# buttons.net
KiCad netlist of a schematic drawn in EAGLE
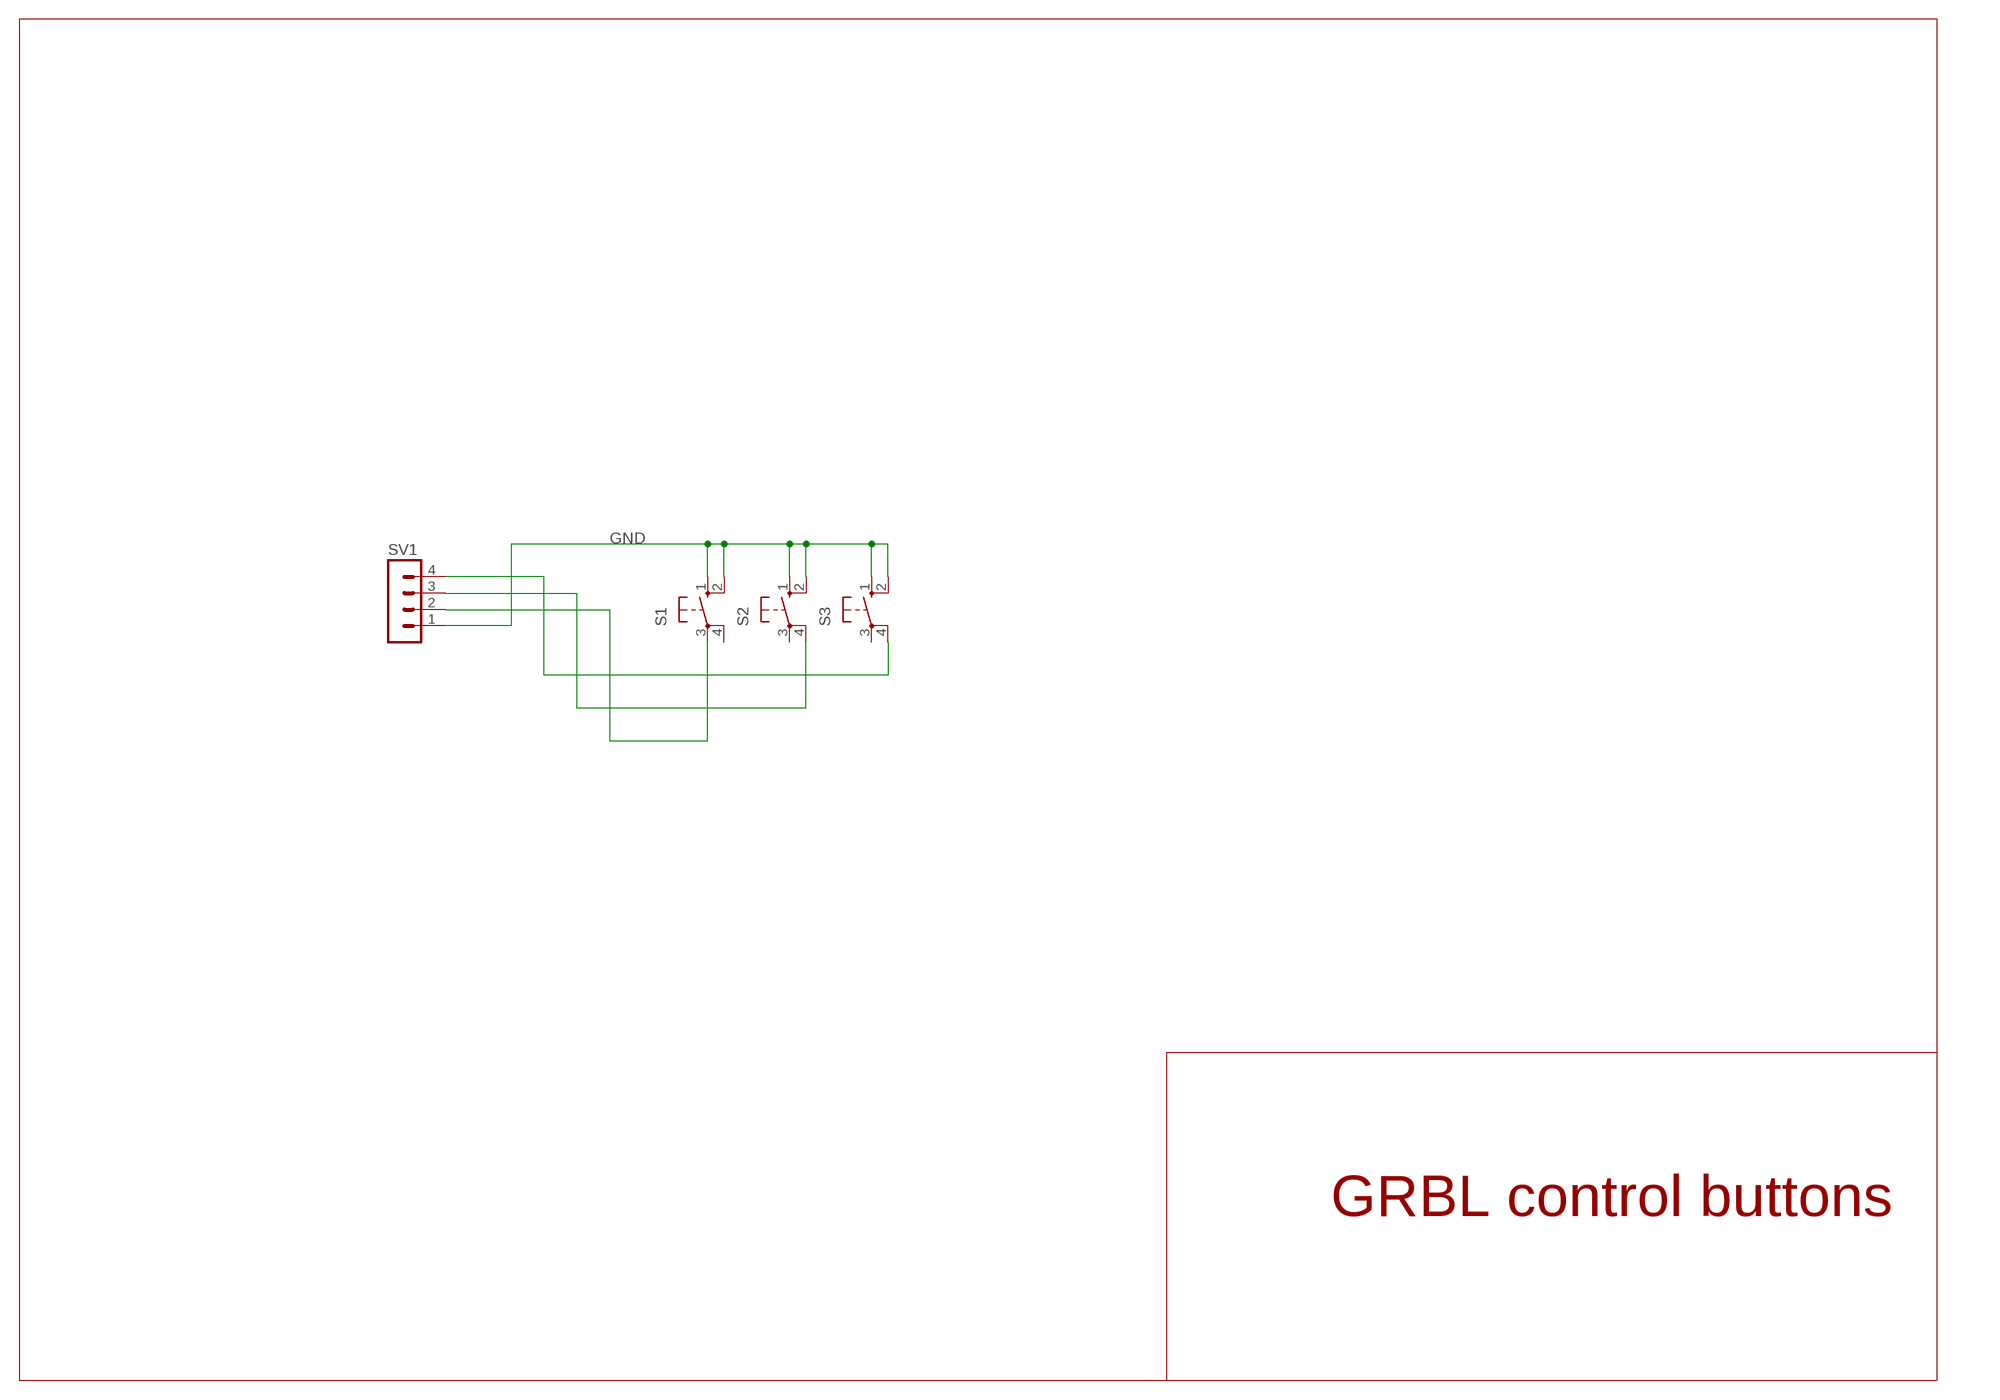
[diagram p0: schematic, sheet 1]
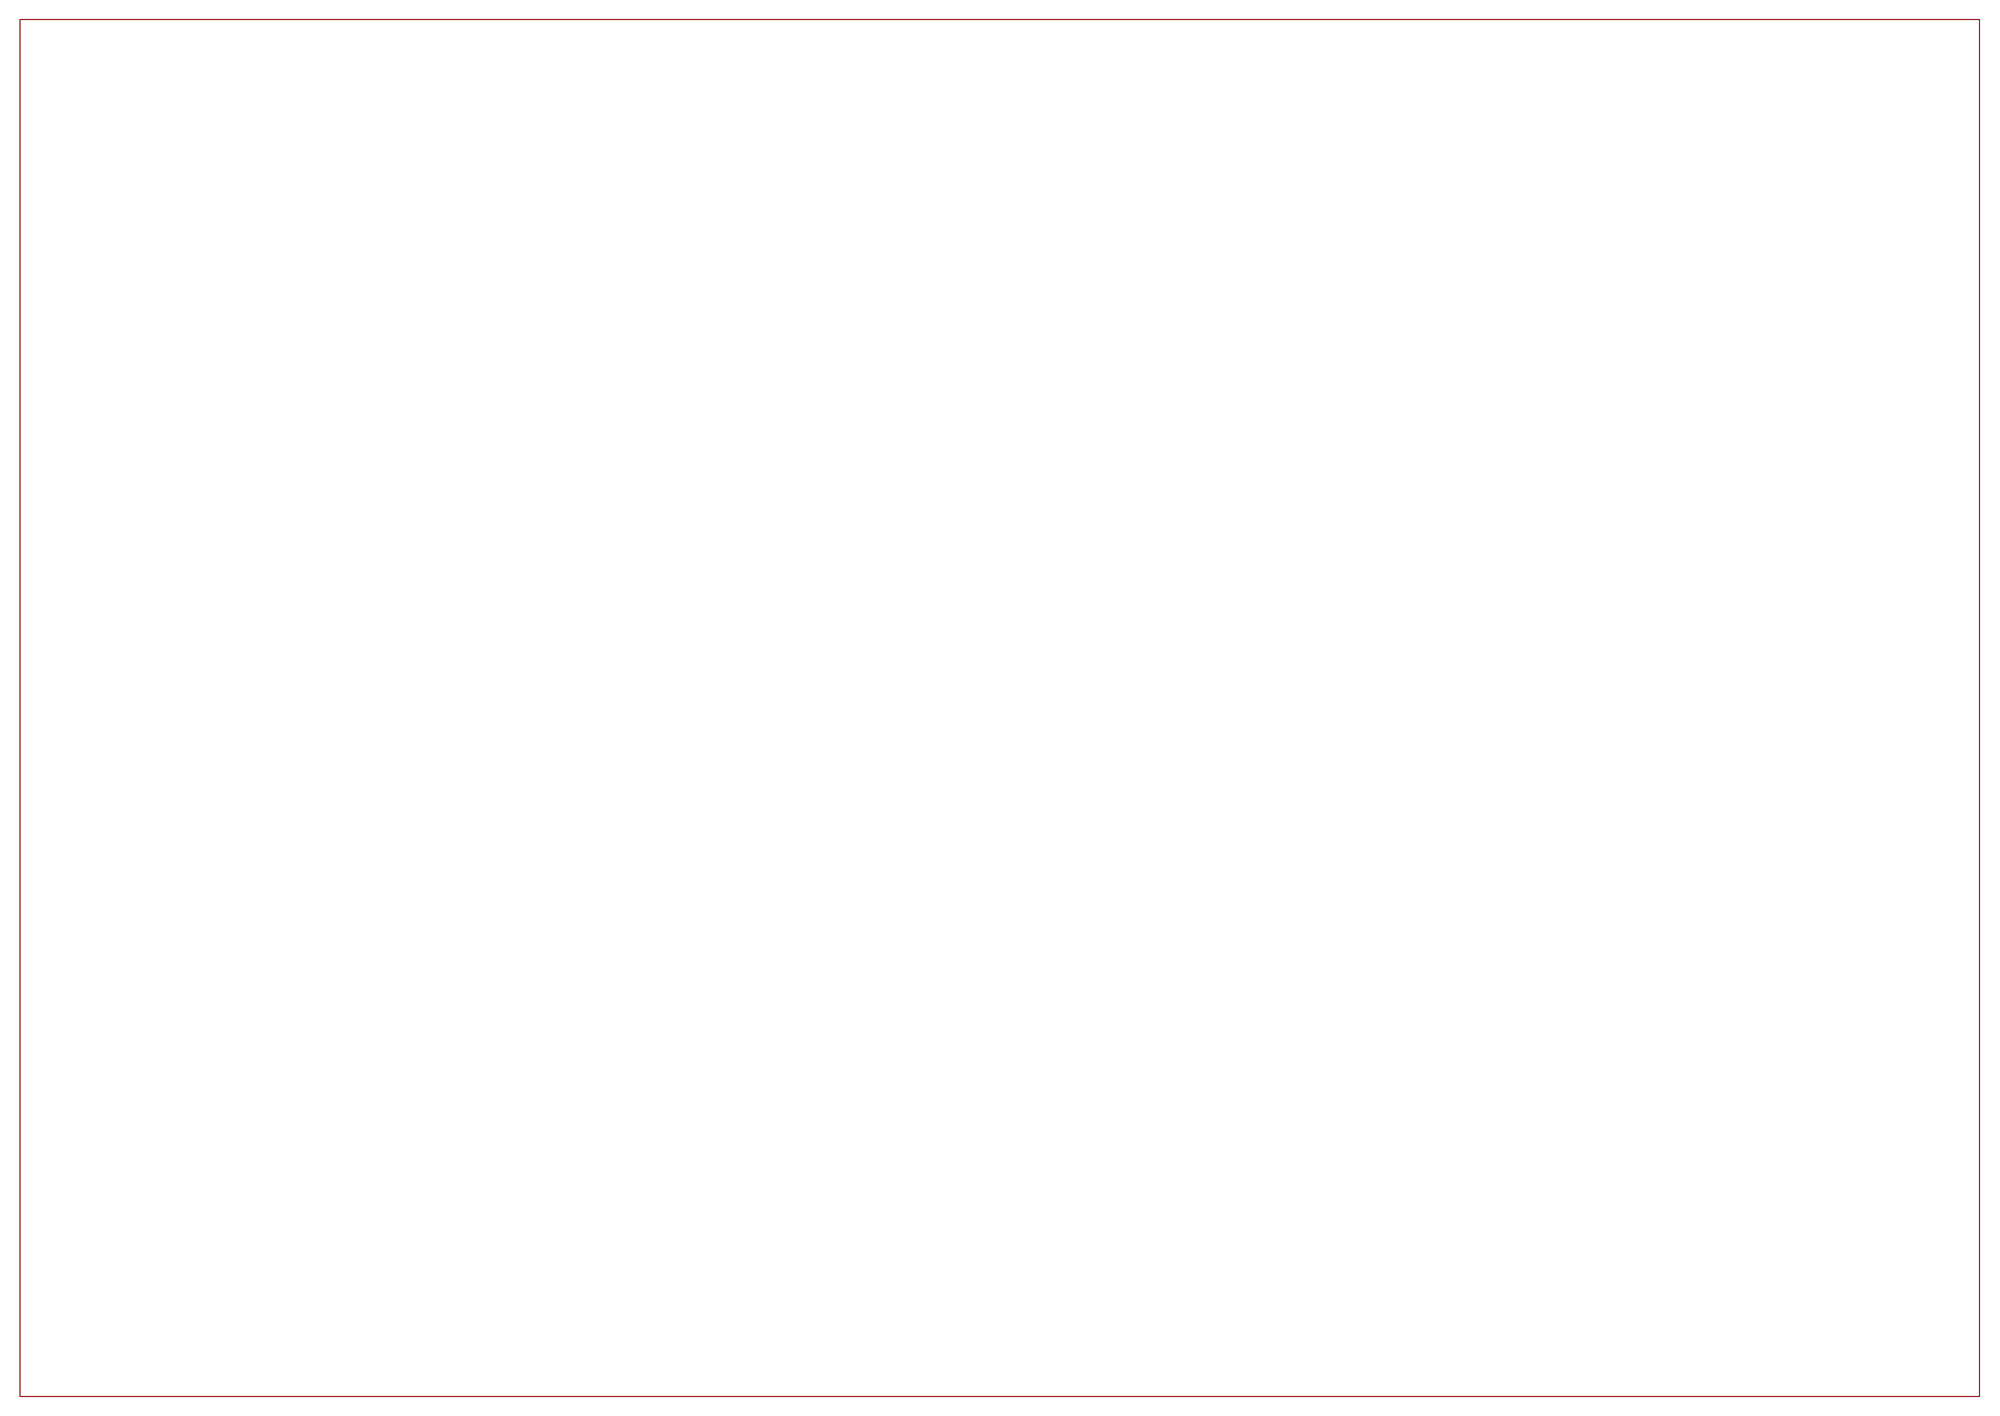
[diagram p1: schematic, sheet 2]

(export (version "E")
  (design (tool "Eeschema 10.0.6"))
  (components
    (comp (ref "S1")
      (value "40-XX")
      (footprint "eagle-import:B3F-40XX")
      (fields (field (name "MF") "OMRON COMPONENTS USA") (field (name "MPN") "B3F-4000"))
      (libsource (lib "eagle-import") (part "40-XX"))
    )
    (comp (ref "S2")
      (value "40-XX")
      (footprint "eagle-import:B3F-40XX")
      (fields (field (name "MF") "OMRON COMPONENTS USA") (field (name "MPN") "B3F-4000"))
      (libsource (lib "eagle-import") (part "40-XX"))
    )
    (comp (ref "S3")
      (value "40-XX")
      (footprint "eagle-import:B3F-40XX")
      (fields (field (name "MF") "OMRON COMPONENTS USA") (field (name "MPN") "B3F-4000"))
      (libsource (lib "eagle-import") (part "40-XX"))
    )
    (comp (ref "SV1")
      (value "MA04-1")
      (footprint "eagle-import:MA04-1")
      (libsource (lib "eagle-import") (part "MA04-1"))
    )
  )
  (nets
    (net (code "1") (name "GND") (class "Default")
      (node (ref "S1") (pin "1") (pinfunction "S_1") (pintype "passive"))
      (node (ref "S1") (pin "2") (pinfunction "S1_2") (pintype "passive"))
      (node (ref "S2") (pin "1") (pinfunction "S_1") (pintype "passive"))
      (node (ref "S2") (pin "2") (pinfunction "S1_2") (pintype "passive"))
      (node (ref "S3") (pin "1") (pinfunction "S_1") (pintype "passive"))
      (node (ref "S3") (pin "2") (pinfunction "S1_2") (pintype "passive"))
      (node (ref "SV1") (pin "1") (pinfunction "1_1") (pintype "passive"))
    )
    (net (code "2") (name "Net-(S1-P)") (class "Default")
      (node (ref "S1") (pin "3") (pinfunction "P_3") (pintype "passive"))
      (node (ref "SV1") (pin "2") (pinfunction "2_2") (pintype "passive"))
    )
    (net (code "3") (name "Net-(S2-P1)") (class "Default")
      (node (ref "S2") (pin "4") (pinfunction "P1_4") (pintype "passive"))
      (node (ref "SV1") (pin "3") (pinfunction "3_3") (pintype "passive"))
    )
    (net (code "4") (name "Net-(S3-P1)") (class "Default")
      (node (ref "S3") (pin "4") (pinfunction "P1_4") (pintype "passive"))
      (node (ref "SV1") (pin "4") (pinfunction "4_4") (pintype "passive"))
    )
    (net (code "5") (name "unconnected-(S1-P1-Pad4)") (class "Default")
      (node (ref "S1") (pin "4") (pinfunction "P1_4") (pintype "passive"))
    )
    (net (code "6") (name "unconnected-(S2-P-Pad3)") (class "Default")
      (node (ref "S2") (pin "3") (pinfunction "P_3") (pintype "passive"))
    )
    (net (code "7") (name "unconnected-(S3-P-Pad3)") (class "Default")
      (node (ref "S3") (pin "3") (pinfunction "P_3") (pintype "passive"))
    )
  )
)
